# design.net
KiCad netlist of a schematic drawn in Altium Designer
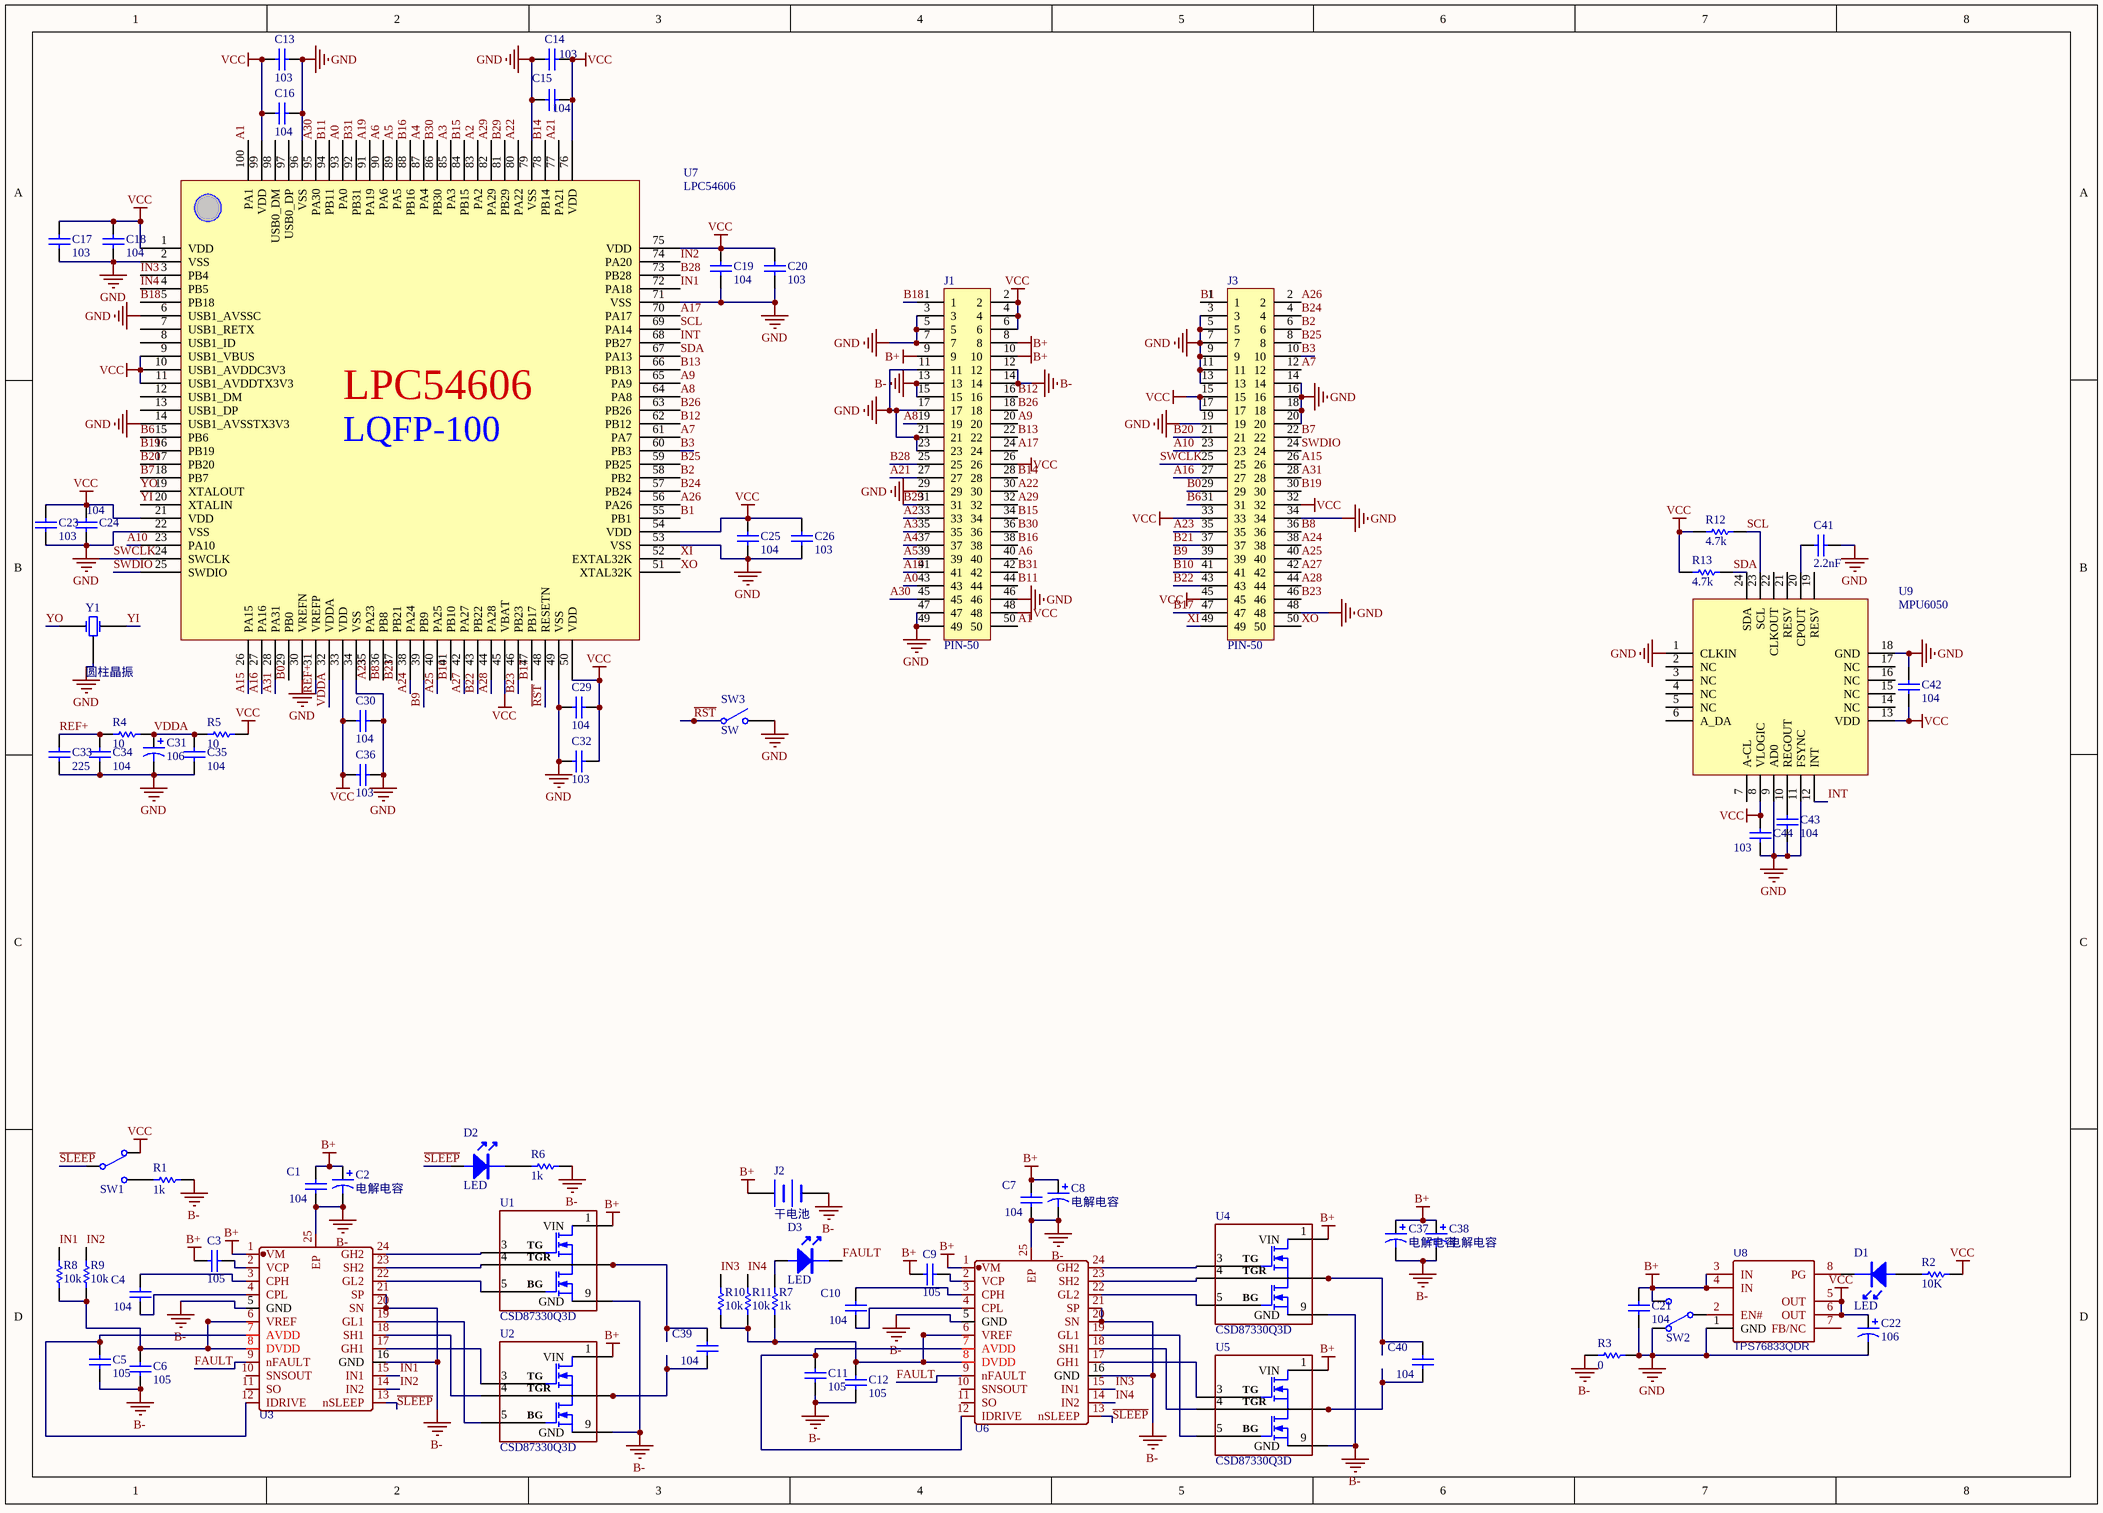
[diagram p0: 原理图.SchDoc]

(export (version "E")
  (design (tool "Eeschema 10.0.6"))
  (components
    (comp (ref "C1")
      (value "104")
      (footprint "C0402")
      (description "Capacitor")
      (fields (field (name "PUBLISHER") "Altium Limited"))
      (libsource (lib "容阻感") (part "电容"))
    )
    (comp (ref "C2")
      (value "电解电容")
      (footprint "贴片电解 4*5.4")
      (description "Polarized Capacitor (Axial)")
      (fields (field (name "PUBLISHER") "Altium Limited"))
      (libsource (lib "容阻感") (part "电解电容"))
    )
    (comp (ref "C3")
      (value "105")
      (footprint "C0603")
      (description "Capacitor")
      (fields (field (name "PUBLISHER") "Altium Limited"))
      (libsource (lib "容阻感") (part "电容"))
    )
    (comp (ref "C4")
      (value "104")
      (footprint "C0402")
      (description "Capacitor")
      (fields (field (name "PUBLISHER") "Altium Limited"))
      (libsource (lib "容阻感") (part "电容"))
    )
    (comp (ref "C5")
      (value "105")
      (footprint "C0402")
      (description "Capacitor")
      (fields (field (name "PUBLISHER") "Altium Limited"))
      (libsource (lib "容阻感") (part "电容"))
    )
    (comp (ref "C6")
      (value "105")
      (footprint "C0402")
      (description "Capacitor")
      (fields (field (name "PUBLISHER") "Altium Limited"))
      (libsource (lib "容阻感") (part "电容"))
    )
    (comp (ref "C7")
      (value "104")
      (footprint "C0402")
      (description "Capacitor")
      (fields (field (name "PUBLISHER") "Altium Limited"))
      (libsource (lib "容阻感") (part "电容"))
    )
    (comp (ref "C8")
      (value "电解电容")
      (footprint "贴片电解 4*5.4")
      (description "Polarized Capacitor (Axial)")
      (fields (field (name "PUBLISHER") "Altium Limited"))
      (libsource (lib "容阻感") (part "电解电容"))
    )
    (comp (ref "C9")
      (value "105")
      (footprint "C0603")
      (description "Capacitor")
      (fields (field (name "PUBLISHER") "Altium Limited"))
      (libsource (lib "容阻感") (part "电容"))
    )
    (comp (ref "C10")
      (value "104")
      (footprint "C0402")
      (description "Capacitor")
      (fields (field (name "PUBLISHER") "Altium Limited"))
      (libsource (lib "容阻感") (part "电容"))
    )
    (comp (ref "C11")
      (value "105")
      (footprint "C0402")
      (description "Capacitor")
      (fields (field (name "PUBLISHER") "Altium Limited"))
      (libsource (lib "容阻感") (part "电容"))
    )
    (comp (ref "C12")
      (value "105")
      (footprint "C0402")
      (description "Capacitor")
      (fields (field (name "PUBLISHER") "Altium Limited"))
      (libsource (lib "容阻感") (part "电容"))
    )
    (comp (ref "C13")
      (value "103")
      (footprint "C0402")
      (description "Capacitor")
      (fields (field (name "PUBLISHER") "Altium Limited"))
      (libsource (lib "容阻感") (part "电容"))
    )
    (comp (ref "C14")
      (value "103")
      (footprint "C0402")
      (description "Capacitor")
      (fields (field (name "PUBLISHER") "Altium Limited"))
      (libsource (lib "容阻感") (part "电容"))
    )
    (comp (ref "C15")
      (value "104")
      (footprint "C0402")
      (description "Capacitor")
      (fields (field (name "PUBLISHER") "Altium Limited"))
      (libsource (lib "容阻感") (part "电容"))
    )
    (comp (ref "C16")
      (value "104")
      (footprint "C0402")
      (description "Capacitor")
      (fields (field (name "PUBLISHER") "Altium Limited"))
      (libsource (lib "容阻感") (part "电容"))
    )
    (comp (ref "C17")
      (value "103")
      (footprint "C0402")
      (description "Capacitor")
      (fields (field (name "PUBLISHER") "Altium Limited"))
      (libsource (lib "容阻感") (part "电容"))
    )
    (comp (ref "C18")
      (value "104")
      (footprint "C0402")
      (description "Capacitor")
      (fields (field (name "PUBLISHER") "Altium Limited"))
      (libsource (lib "容阻感") (part "电容"))
    )
    (comp (ref "C19")
      (value "104")
      (footprint "C0402")
      (description "Capacitor")
      (fields (field (name "PUBLISHER") "Altium Limited"))
      (libsource (lib "容阻感") (part "电容"))
    )
    (comp (ref "C20")
      (value "103")
      (footprint "C0402")
      (description "Capacitor")
      (fields (field (name "PUBLISHER") "Altium Limited"))
      (libsource (lib "容阻感") (part "电容"))
    )
    (comp (ref "C21")
      (value "104")
      (footprint "C0402")
      (description "Capacitor")
      (fields (field (name "PUBLISHER") "Altium Limited"))
      (libsource (lib "容阻感") (part "电容"))
    )
    (comp (ref "C22")
      (value "106")
      (footprint "3216-ce")
      (description "Polarized Capacitor (Axial)")
      (fields (field (name "PUBLISHER") "Altium Limited"))
      (libsource (lib "容阻感") (part "电解电容"))
    )
    (comp (ref "C23")
      (value "103")
      (footprint "C0402")
      (description "Capacitor")
      (fields (field (name "PUBLISHER") "Altium Limited"))
      (libsource (lib "容阻感") (part "电容"))
    )
    (comp (ref "C24")
      (value "104")
      (footprint "C0402")
      (description "Capacitor")
      (fields (field (name "PUBLISHER") "Altium Limited"))
      (libsource (lib "容阻感") (part "电容"))
    )
    (comp (ref "C25")
      (value "104")
      (footprint "C0402")
      (description "Capacitor")
      (fields (field (name "PUBLISHER") "Altium Limited"))
      (libsource (lib "容阻感") (part "电容"))
    )
    (comp (ref "C26")
      (value "103")
      (footprint "C0402")
      (description "Capacitor")
      (fields (field (name "PUBLISHER") "Altium Limited"))
      (libsource (lib "容阻感") (part "电容"))
    )
    (comp (ref "C29")
      (value "104")
      (footprint "C0402")
      (description "Capacitor")
      (fields (field (name "PUBLISHER") "Altium Limited"))
      (libsource (lib "容阻感") (part "电容"))
    )
    (comp (ref "C30")
      (value "104")
      (footprint "C0402")
      (description "Capacitor")
      (fields (field (name "PUBLISHER") "Altium Limited"))
      (libsource (lib "容阻感") (part "电容"))
    )
    (comp (ref "C31")
      (value "106")
      (footprint "3216-ce")
      (description "Polarized Capacitor (Axial)")
      (fields (field (name "PUBLISHER") "Altium Limited"))
      (libsource (lib "容阻感") (part "电解电容"))
    )
    (comp (ref "C32")
      (value "103")
      (footprint "C0402")
      (description "Capacitor")
      (fields (field (name "PUBLISHER") "Altium Limited"))
      (libsource (lib "容阻感") (part "电容"))
    )
    (comp (ref "C33")
      (value "225")
      (footprint "C0603")
      (description "Capacitor")
      (fields (field (name "PUBLISHER") "Altium Limited"))
      (libsource (lib "容阻感") (part "电容"))
    )
    (comp (ref "C34")
      (value "104")
      (footprint "C0402")
      (description "Capacitor")
      (fields (field (name "PUBLISHER") "Altium Limited"))
      (libsource (lib "容阻感") (part "电容"))
    )
    (comp (ref "C35")
      (value "104")
      (footprint "C0402")
      (description "Capacitor")
      (fields (field (name "PUBLISHER") "Altium Limited"))
      (libsource (lib "容阻感") (part "电容"))
    )
    (comp (ref "C36")
      (value "103")
      (footprint "C0402")
      (description "Capacitor")
      (fields (field (name "PUBLISHER") "Altium Limited"))
      (libsource (lib "容阻感") (part "电容"))
    )
    (comp (ref "C37")
      (value "电解电容")
      (footprint "贴片电解 4*5.4")
      (description "Polarized Capacitor (Axial)")
      (fields (field (name "PUBLISHER") "Altium Limited"))
      (libsource (lib "容阻感") (part "电解电容"))
    )
    (comp (ref "C38")
      (value "电解电容")
      (footprint "贴片电解 4*5.4")
      (description "Polarized Capacitor (Axial)")
      (fields (field (name "PUBLISHER") "Altium Limited"))
      (libsource (lib "容阻感") (part "电解电容"))
    )
    (comp (ref "C39")
      (value "104")
      (footprint "C0402")
      (description "Capacitor")
      (fields (field (name "PUBLISHER") "Altium Limited"))
      (libsource (lib "容阻感") (part "电容"))
    )
    (comp (ref "C40")
      (value "104")
      (footprint "C0402")
      (description "Capacitor")
      (fields (field (name "PUBLISHER") "Altium Limited"))
      (libsource (lib "容阻感") (part "电容"))
    )
    (comp (ref "C41")
      (value "2.2nF")
      (footprint "C0402")
      (description "Capacitor")
      (fields (field (name "PUBLISHER") "Altium Limited"))
      (libsource (lib "容阻感") (part "电容"))
    )
    (comp (ref "C42")
      (value "104")
      (footprint "C0402")
      (description "Capacitor")
      (fields (field (name "PUBLISHER") "Altium Limited"))
      (libsource (lib "容阻感") (part "电容"))
    )
    (comp (ref "C43")
      (value "104")
      (footprint "C0402")
      (description "Capacitor")
      (fields (field (name "PUBLISHER") "Altium Limited"))
      (libsource (lib "容阻感") (part "电容"))
    )
    (comp (ref "C44")
      (value "103")
      (footprint "C0402")
      (description "Capacitor")
      (fields (field (name "PUBLISHER") "Altium Limited"))
      (libsource (lib "容阻感") (part "电容"))
    )
    (comp (ref "D1") (value "LED") (footprint "LED 0603G") (libsource (lib "管子、") (part "LED")))
    (comp (ref "D2") (value "LED") (footprint "LED 0603G") (libsource (lib "管子、") (part "LED")))
    (comp (ref "D3") (value "LED") (footprint "LED 0603G") (libsource (lib "管子、") (part "LED")))
    (comp (ref "J1") (value "PIN-50") (footprint "50PDF12-0.5母") (libsource (lib "接插件") (part "PIN-50")))
    (comp (ref "J2")
      (value "干电池")
      (footprint "T接头")
      (description "Battery")
      (libsource (lib "接插件") (part "干电池"))
    )
    (comp (ref "J3") (value "PIN-50") (footprint "50PDF12-0.5母") (libsource (lib "接插件") (part "PIN-50")))
    (comp (ref "R1")
      (value "1k")
      (footprint "R0402")
      (description "Resistor")
      (fields (field (name "PUBLISHER") "Altium Limited"))
      (libsource (lib "容阻感") (part "电阻"))
    )
    (comp (ref "R2")
      (value "10K")
      (footprint "R0402")
      (description "Resistor")
      (fields (field (name "PUBLISHER") "Altium Limited"))
      (libsource (lib "容阻感") (part "电阻"))
    )
    (comp (ref "R3")
      (value "0")
      (footprint "R0603")
      (description "Resistor")
      (fields (field (name "PUBLISHER") "Altium Limited"))
      (libsource (lib "容阻感") (part "电阻"))
    )
    (comp (ref "R4")
      (value "10")
      (footprint "R0603")
      (description "Resistor")
      (fields (field (name "PUBLISHER") "Altium Limited"))
      (libsource (lib "容阻感") (part "电阻"))
    )
    (comp (ref "R5")
      (value "10")
      (footprint "R0603")
      (description "Resistor")
      (fields (field (name "PUBLISHER") "Altium Limited"))
      (libsource (lib "容阻感") (part "电阻"))
    )
    (comp (ref "R6")
      (value "1k")
      (footprint "R0402")
      (description "Resistor")
      (fields (field (name "PUBLISHER") "Altium Limited"))
      (libsource (lib "容阻感") (part "电阻"))
    )
    (comp (ref "R7")
      (value "1k")
      (footprint "R0402")
      (description "Resistor")
      (fields (field (name "PUBLISHER") "Altium Limited"))
      (libsource (lib "容阻感") (part "电阻"))
    )
    (comp (ref "R8")
      (value "10k")
      (footprint "R0402")
      (description "Resistor")
      (fields (field (name "PUBLISHER") "Altium Limited"))
      (libsource (lib "容阻感") (part "电阻"))
    )
    (comp (ref "R9")
      (value "10k")
      (footprint "R0402")
      (description "Resistor")
      (fields (field (name "PUBLISHER") "Altium Limited"))
      (libsource (lib "容阻感") (part "电阻"))
    )
    (comp (ref "R10")
      (value "10k")
      (footprint "R0402")
      (description "Resistor")
      (fields (field (name "PUBLISHER") "Altium Limited"))
      (libsource (lib "容阻感") (part "电阻"))
    )
    (comp (ref "R11")
      (value "10k")
      (footprint "R0402")
      (description "Resistor")
      (fields (field (name "PUBLISHER") "Altium Limited"))
      (libsource (lib "容阻感") (part "电阻"))
    )
    (comp (ref "R12")
      (value "4.7k")
      (footprint "R0402")
      (description "Resistor")
      (fields (field (name "PUBLISHER") "Altium Limited"))
      (libsource (lib "容阻感") (part "电阻"))
    )
    (comp (ref "R13")
      (value "4.7k")
      (footprint "R0402")
      (description "Resistor")
      (fields (field (name "PUBLISHER") "Altium Limited"))
      (libsource (lib "容阻感") (part "电阻"))
    )
    (comp (ref "SW1")
      (value "K3-1235S-K1")
      (footprint "K3-1235S-K1")
      (description "Switch")
      (libsource (lib "接插件") (part "单刀双掷"))
    )
    (comp (ref "SW2")
      (value "K3-1235S-K1")
      (footprint "K3-1235S-K1")
      (description "Switch")
      (libsource (lib "接插件") (part "单刀双掷"))
    )
    (comp (ref "SW3")
      (value "SW")
      (footprint "按键微动开关2")
      (description "Single-Pole, Single-Throw Switch")
      (libsource (lib "接插件") (part "Switch"))
    )
    (comp (ref "U1")
      (value "CSD87330Q3D")
      (footprint "LSON-CLIP-8")
      (description "半桥NMOS")
      (libsource (lib "IC") (part "CSD87330Q3D"))
    )
    (comp (ref "U2")
      (value "CSD87330Q3D")
      (footprint "LSON-CLIP-8")
      (description "半桥NMOS")
      (libsource (lib "IC") (part "CSD87330Q3D"))
    )
    (comp (ref "U3")
      (value "DRV8701ERGET")
      (footprint "VQFN-24_24PIN-L4.00-W4.00-PITCH0.50-EP-TL")
      (description "H桥驱动")
      (fields (field (name "BOM_SUPPLIER PART") "C132049") (field (name "CONTRIBUTOR") "LCSC"))
      (libsource (lib "IC") (part "DRV8701"))
    )
    (comp (ref "U4")
      (value "CSD87330Q3D")
      (footprint "LSON-CLIP-8")
      (description "半桥NMOS")
      (libsource (lib "IC") (part "CSD87330Q3D"))
    )
    (comp (ref "U5")
      (value "CSD87330Q3D")
      (footprint "LSON-CLIP-8")
      (description "半桥NMOS")
      (libsource (lib "IC") (part "CSD87330Q3D"))
    )
    (comp (ref "U6")
      (value "DRV8701ERGET")
      (footprint "VQFN-24_24PIN-L4.00-W4.00-PITCH0.50-EP-TL")
      (description "H桥驱动")
      (fields (field (name "BOM_SUPPLIER PART") "C132049") (field (name "CONTRIBUTOR") "LCSC"))
      (libsource (lib "IC") (part "DRV8701"))
    )
    (comp (ref "U7") (value "LPC54606") (footprint "LQFP100") (libsource (lib "IC") (part "LPC54606BD100")))
    (comp (ref "U8")
      (value "TPS76833QDR")
      (footprint "SOIC8-3.9MM")
      (fields (field (name "BOM_SUPPLIER PART") "C16002"))
      (libsource (lib "IC") (part "TPS76833QDR"))
    )
    (comp (ref "U9") (value "MPU6050") (footprint "QFN-24_4x4x05P") (libsource (lib "IC") (part "MPU6050")))
    (comp (ref "Y1")
      (value "圆柱晶振")
      (footprint "OSC-3213CSTSE800G52-R0")
      (libsource (lib "IC") (part "XTAL_3Pin"))
    )
  )
  (nets
    (net (code "1") (name "/A0") (class "Default")
      (node (ref "J1") (pin "43") (pinfunction "43_43") (pintype "passive"))
      (node (ref "U7") (pin "93") (pinfunction "PA0_93") (pintype "passive"))
    )
    (net (code "2") (name "/A1") (class "Default")
      (node (ref "J1") (pin "50") (pinfunction "50_50") (pintype "passive"))
      (node (ref "U7") (pin "100") (pinfunction "PA1_100") (pintype "passive"))
    )
    (net (code "3") (name "/A2") (class "Default")
      (node (ref "J1") (pin "33") (pinfunction "33_33") (pintype "passive"))
      (node (ref "U7") (pin "83") (pinfunction "PA2_83") (pintype "passive"))
    )
    (net (code "4") (name "/A3") (class "Default")
      (node (ref "J1") (pin "35") (pinfunction "35_35") (pintype "passive"))
      (node (ref "U7") (pin "85") (pinfunction "PA3_85") (pintype "passive"))
    )
    (net (code "5") (name "/A4") (class "Default")
      (node (ref "J1") (pin "37") (pinfunction "37_37") (pintype "passive"))
      (node (ref "U7") (pin "87") (pinfunction "PA4_87") (pintype "passive"))
    )
    (net (code "6") (name "/A5") (class "Default")
      (node (ref "J1") (pin "39") (pinfunction "39_39") (pintype "passive"))
      (node (ref "U7") (pin "89") (pinfunction "PA5_89") (pintype "passive"))
    )
    (net (code "7") (name "/A6") (class "Default")
      (node (ref "J1") (pin "40") (pinfunction "40_40") (pintype "passive"))
      (node (ref "U7") (pin "90") (pinfunction "PA6_90") (pintype "passive"))
    )
    (net (code "8") (name "/A7") (class "Default")
      (node (ref "J3") (pin "12") (pinfunction "12_12") (pintype "passive"))
      (node (ref "U7") (pin "61") (pinfunction "PA7_61") (pintype "passive"))
    )
    (net (code "9") (name "/A8") (class "Default")
      (node (ref "J1") (pin "19") (pinfunction "19_19") (pintype "passive"))
      (node (ref "U7") (pin "64") (pinfunction "PA8_64") (pintype "passive"))
    )
    (net (code "10") (name "/A9") (class "Default")
      (node (ref "J1") (pin "20") (pinfunction "20_20") (pintype "passive"))
      (node (ref "U7") (pin "65") (pinfunction "PA9_65") (pintype "passive"))
    )
    (net (code "11") (name "/A10") (class "Default")
      (node (ref "J3") (pin "23") (pinfunction "23_23") (pintype "passive"))
      (node (ref "U7") (pin "23") (pinfunction "PA10_23") (pintype "passive"))
    )
    (net (code "12") (name "/A15") (class "Default")
      (node (ref "J3") (pin "26") (pinfunction "26_26") (pintype "passive"))
      (node (ref "U7") (pin "26") (pinfunction "PA15_26") (pintype "passive"))
    )
    (net (code "13") (name "/A16") (class "Default")
      (node (ref "J3") (pin "27") (pinfunction "27_27") (pintype "passive"))
      (node (ref "U7") (pin "27") (pinfunction "PA16_27") (pintype "passive"))
    )
    (net (code "14") (name "/A17") (class "Default")
      (node (ref "J1") (pin "24") (pinfunction "24_24") (pintype "passive"))
      (node (ref "U7") (pin "70") (pinfunction "PA17_70") (pintype "passive"))
    )
    (net (code "15") (name "/A19") (class "Default")
      (node (ref "J1") (pin "41") (pinfunction "41_41") (pintype "passive"))
      (node (ref "U7") (pin "91") (pinfunction "PA19_91") (pintype "passive"))
    )
    (net (code "16") (name "/A21") (class "Default")
      (node (ref "J1") (pin "27") (pinfunction "27_27") (pintype "passive"))
      (node (ref "U7") (pin "77") (pinfunction "PA21_77") (pintype "passive"))
    )
    (net (code "17") (name "/A22") (class "Default")
      (node (ref "J1") (pin "30") (pinfunction "30_30") (pintype "passive"))
      (node (ref "U7") (pin "80") (pinfunction "PA22_80") (pintype "passive"))
    )
    (net (code "18") (name "/A23") (class "Default")
      (node (ref "J3") (pin "35") (pinfunction "35_35") (pintype "passive"))
      (node (ref "U7") (pin "35") (pinfunction "PA23_35") (pintype "passive"))
    )
    (net (code "19") (name "/A24") (class "Default")
      (node (ref "J3") (pin "38") (pinfunction "38_38") (pintype "passive"))
      (node (ref "U7") (pin "38") (pinfunction "PA24_38") (pintype "passive"))
    )
    (net (code "20") (name "/A25") (class "Default")
      (node (ref "J3") (pin "40") (pinfunction "40_40") (pintype "passive"))
      (node (ref "U7") (pin "40") (pinfunction "PA25_40") (pintype "passive"))
    )
    (net (code "21") (name "/A26") (class "Default")
      (node (ref "J3") (pin "2") (pinfunction "2_2") (pintype "passive"))
      (node (ref "U7") (pin "56") (pinfunction "PA26_56") (pintype "passive"))
    )
    (net (code "22") (name "/A27") (class "Default")
      (node (ref "J3") (pin "42") (pinfunction "42_42") (pintype "passive"))
      (node (ref "U7") (pin "42") (pinfunction "PA27_42") (pintype "passive"))
    )
    (net (code "23") (name "/A28") (class "Default")
      (node (ref "J3") (pin "44") (pinfunction "44_44") (pintype "passive"))
      (node (ref "U7") (pin "44") (pinfunction "PA28_44") (pintype "passive"))
    )
    (net (code "24") (name "/A29") (class "Default")
      (node (ref "J1") (pin "32") (pinfunction "32_32") (pintype "passive"))
      (node (ref "U7") (pin "82") (pinfunction "PA29_82") (pintype "passive"))
    )
    (net (code "25") (name "/A30") (class "Default")
      (node (ref "J1") (pin "45") (pinfunction "45_45") (pintype "passive"))
      (node (ref "U7") (pin "95") (pinfunction "PA30_95") (pintype "passive"))
    )
    (net (code "26") (name "/A31") (class "Default")
      (node (ref "J3") (pin "28") (pinfunction "28_28") (pintype "passive"))
      (node (ref "U7") (pin "28") (pinfunction "PA31_28") (pintype "passive"))
    )
    (net (code "27") (name "/B0") (class "Default")
      (node (ref "J3") (pin "29") (pinfunction "29_29") (pintype "passive"))
      (node (ref "U7") (pin "29") (pinfunction "PB0_29") (pintype "passive"))
    )
    (net (code "28") (name "/B1") (class "Default")
      (node (ref "J3") (pin "1") (pinfunction "1_1") (pintype "passive"))
      (node (ref "U7") (pin "55") (pinfunction "PB1_55") (pintype "passive"))
    )
    (net (code "29") (name "/B2") (class "Default")
      (node (ref "J3") (pin "6") (pinfunction "6_6") (pintype "passive"))
      (node (ref "U7") (pin "58") (pinfunction "PB2_58") (pintype "passive"))
    )
    (net (code "30") (name "/B3") (class "Default")
      (node (ref "J3") (pin "10") (pinfunction "10_10") (pintype "passive"))
      (node (ref "U7") (pin "60") (pinfunction "PB3_60") (pintype "passive"))
    )
    (net (code "31") (name "/B6") (class "Default")
      (node (ref "J3") (pin "31") (pinfunction "31_31") (pintype "passive"))
      (node (ref "U7") (pin "15") (pinfunction "PB6_15") (pintype "passive"))
    )
    (net (code "32") (name "/B7") (class "Default")
      (node (ref "J3") (pin "22") (pinfunction "22_22") (pintype "passive"))
      (node (ref "U7") (pin "18") (pinfunction "PB7_18") (pintype "passive"))
    )
    (net (code "33") (name "/B8") (class "Default")
      (node (ref "J3") (pin "36") (pinfunction "36_36") (pintype "passive"))
      (node (ref "U7") (pin "36") (pinfunction "PB8_36") (pintype "passive"))
    )
    (net (code "34") (name "/B9") (class "Default")
      (node (ref "J3") (pin "39") (pinfunction "39_39") (pintype "passive"))
      (node (ref "U7") (pin "39") (pinfunction "PB9_39") (pintype "passive"))
    )
    (net (code "35") (name "/B10") (class "Default")
      (node (ref "J3") (pin "41") (pinfunction "41_41") (pintype "passive"))
      (node (ref "U7") (pin "41") (pinfunction "PB10_41") (pintype "passive"))
    )
    (net (code "36") (name "/B11") (class "Default")
      (node (ref "J1") (pin "44") (pinfunction "44_44") (pintype "passive"))
      (node (ref "U7") (pin "94") (pinfunction "PB11_94") (pintype "passive"))
    )
    (net (code "37") (name "/B12") (class "Default")
      (node (ref "J1") (pin "16") (pinfunction "16_16") (pintype "passive"))
      (node (ref "U7") (pin "62") (pinfunction "PB12_62") (pintype "passive"))
    )
    (net (code "38") (name "/B13") (class "Default")
      (node (ref "J1") (pin "22") (pinfunction "22_22") (pintype "passive"))
      (node (ref "U7") (pin "66") (pinfunction "PB13_66") (pintype "passive"))
    )
    (net (code "39") (name "/B14") (class "Default")
      (node (ref "J1") (pin "28") (pinfunction "28_28") (pintype "passive"))
      (node (ref "U7") (pin "78") (pinfunction "PB14_78") (pintype "passive"))
    )
    (net (code "40") (name "/B15") (class "Default")
      (node (ref "J1") (pin "34") (pinfunction "34_34") (pintype "passive"))
      (node (ref "U7") (pin "84") (pinfunction "PB15_84") (pintype "passive"))
    )
    (net (code "41") (name "/B16") (class "Default")
      (node (ref "J1") (pin "38") (pinfunction "38_38") (pintype "passive"))
      (node (ref "U7") (pin "88") (pinfunction "PB16_88") (pintype "passive"))
    )
    (net (code "42") (name "/B17") (class "Default")
      (node (ref "J3") (pin "47") (pinfunction "47_47") (pintype "passive"))
      (node (ref "U7") (pin "47") (pinfunction "PB17_47") (pintype "passive"))
    )
    (net (code "43") (name "/B18") (class "Default")
      (node (ref "J1") (pin "1") (pinfunction "1_1") (pintype "passive"))
      (node (ref "U7") (pin "5") (pinfunction "PB18_5") (pintype "passive"))
    )
    (net (code "44") (name "/B19") (class "Default")
      (node (ref "J3") (pin "30") (pinfunction "30_30") (pintype "passive"))
      (node (ref "U7") (pin "16") (pinfunction "PB19_16") (pintype "passive"))
    )
    (net (code "45") (name "/B20") (class "Default")
      (node (ref "J3") (pin "21") (pinfunction "21_21") (pintype "passive"))
      (node (ref "U7") (pin "17") (pinfunction "PB20_17") (pintype "passive"))
    )
    (net (code "46") (name "/B21") (class "Default")
      (node (ref "J3") (pin "37") (pinfunction "37_37") (pintype "passive"))
      (node (ref "U7") (pin "37") (pinfunction "PB21_37") (pintype "passive"))
    )
    (net (code "47") (name "/B22") (class "Default")
      (node (ref "J3") (pin "43") (pinfunction "43_43") (pintype "passive"))
      (node (ref "U7") (pin "43") (pinfunction "PB22_43") (pintype "passive"))
    )
    (net (code "48") (name "/B23") (class "Default")
      (node (ref "J3") (pin "46") (pinfunction "46_46") (pintype "passive"))
      (node (ref "U7") (pin "46") (pinfunction "PB23_46") (pintype "passive"))
    )
    (net (code "49") (name "/B24") (class "Default")
      (node (ref "J3") (pin "4") (pinfunction "4_4") (pintype "passive"))
      (node (ref "U7") (pin "57") (pinfunction "PB24_57") (pintype "passive"))
    )
    (net (code "50") (name "/B25") (class "Default")
      (node (ref "J3") (pin "8") (pinfunction "8_8") (pintype "passive"))
      (node (ref "U7") (pin "59") (pinfunction "PB25_59") (pintype "passive"))
    )
    (net (code "51") (name "/B26") (class "Default")
      (node (ref "J1") (pin "18") (pinfunction "18_18") (pintype "passive"))
      (node (ref "U7") (pin "63") (pinfunction "PB26_63") (pintype "passive"))
    )
    (net (code "52") (name "/B28") (class "Default")
      (node (ref "J1") (pin "25") (pinfunction "25_25") (pintype "passive"))
      (node (ref "U7") (pin "73") (pinfunction "PB28_73") (pintype "passive"))
    )
    (net (code "53") (name "/B29") (class "Default")
      (node (ref "J1") (pin "31") (pinfunction "31_31") (pintype "passive"))
      (node (ref "U7") (pin "81") (pinfunction "PB29_81") (pintype "passive"))
    )
    (net (code "54") (name "/B30") (class "Default")
      (node (ref "J1") (pin "36") (pinfunction "36_36") (pintype "passive"))
      (node (ref "U7") (pin "86") (pinfunction "PB30_86") (pintype "passive"))
    )
    (net (code "55") (name "/B31") (class "Default")
      (node (ref "J1") (pin "42") (pinfunction "42_42") (pintype "passive"))
      (node (ref "U7") (pin "92") (pinfunction "PB31_92") (pintype "passive"))
    )
    (net (code "56") (name "/FAULT") (class "Default")
      (node (ref "D3") (pin "K") (pinfunction "2_K") (pintype "passive"))
      (node (ref "U3") (pin "9") (pinfunction "nFAULT_9") (pintype "passive"))
      (node (ref "U6") (pin "9") (pinfunction "nFAULT_9") (pintype "passive"))
    )
    (net (code "57") (name "/IN1") (class "Default")
      (node (ref "R8") (pin "1") (pinfunction "1_1") (pintype "passive"))
      (node (ref "U3") (pin "15") (pinfunction "IN1_15") (pintype "passive"))
      (node (ref "U7") (pin "72") (pinfunction "PA18_72") (pintype "passive"))
    )
    (net (code "58") (name "/IN2") (class "Default")
      (node (ref "R9") (pin "1") (pinfunction "1_1") (pintype "passive"))
      (node (ref "U3") (pin "14") (pinfunction "IN2_14") (pintype "passive"))
      (node (ref "U7") (pin "74") (pinfunction "PA20_74") (pintype "passive"))
    )
    (net (code "59") (name "/IN3") (class "Default")
      (node (ref "R10") (pin "1") (pinfunction "1_1") (pintype "passive"))
      (node (ref "U6") (pin "15") (pinfunction "IN1_15") (pintype "passive"))
      (node (ref "U7") (pin "3") (pinfunction "PB4_3") (pintype "passive"))
    )
    (net (code "60") (name "/IN4") (class "Default")
      (node (ref "R11") (pin "1") (pinfunction "1_1") (pintype "passive"))
      (node (ref "U6") (pin "14") (pinfunction "IN2_14") (pintype "passive"))
      (node (ref "U7") (pin "4") (pinfunction "PB5_4") (pintype "passive"))
    )
    (net (code "61") (name "/INT") (class "Default")
      (node (ref "U7") (pin "68") (pinfunction "PB27_68") (pintype "passive"))
      (node (ref "U9") (pin "12") (pinfunction "INT_12") (pintype "passive"))
    )
    (net (code "62") (name "/REF+") (class "Default")
      (node (ref "C33") (pin "2") (pinfunction "2_2") (pintype "passive"))
      (node (ref "C34") (pin "2") (pinfunction "2_2") (pintype "passive"))
      (node (ref "R4") (pin "2") (pinfunction "2_2") (pintype "passive"))
      (node (ref "U7") (pin "31") (pinfunction "VREFP_31") (pintype "passive"))
    )
    (net (code "63") (name "/RST") (class "Default")
      (node (ref "SW3") (pin "1") (pinfunction "COMMON_1") (pintype "passive"))
      (node (ref "U7") (pin "48") (pinfunction "RESETN_48") (pintype "passive"))
    )
    (net (code "64") (name "/SCL") (class "Default")
      (node (ref "R12") (pin "2") (pinfunction "2_2") (pintype "passive"))
      (node (ref "U7") (pin "69") (pinfunction "PA14_69") (pintype "passive"))
      (node (ref "U9") (pin "23") (pinfunction "SCL_23") (pintype "passive"))
    )
    (net (code "65") (name "/SDA") (class "Default")
      (node (ref "R13") (pin "2") (pinfunction "2_2") (pintype "passive"))
      (node (ref "U7") (pin "67") (pinfunction "PA13_67") (pintype "passive"))
      (node (ref "U9") (pin "24") (pinfunction "SDA_24") (pintype "passive"))
    )
    (net (code "66") (name "/SLEEP") (class "Default")
      (node (ref "D2") (pin "A") (pinfunction "1_A") (pintype "passive"))
      (node (ref "SW1") (pin "2") (pinfunction "2_2") (pintype "passive"))
      (node (ref "U3") (pin "13") (pinfunction "nSLEEP_13") (pintype "passive"))
      (node (ref "U6") (pin "13") (pinfunction "nSLEEP_13") (pintype "passive"))
    )
    (net (code "67") (name "/SWCLK") (class "Default")
      (node (ref "J3") (pin "25") (pinfunction "25_25") (pintype "passive"))
      (node (ref "U7") (pin "24") (pinfunction "SWCLK_24") (pintype "passive"))
    )
    (net (code "68") (name "/SWDIO") (class "Default")
      (node (ref "J3") (pin "24") (pinfunction "24_24") (pintype "passive"))
      (node (ref "U7") (pin "25") (pinfunction "SWDIO_25") (pintype "passive"))
    )
    (net (code "69") (name "/VDDA") (class "Default")
      (node (ref "C31") (pin "1") (pinfunction "1_1") (pintype "passive"))
      (node (ref "C35") (pin "2") (pinfunction "2_2") (pintype "passive"))
      (node (ref "R4") (pin "1") (pinfunction "1_1") (pintype "passive"))
      (node (ref "R5") (pin "2") (pinfunction "2_2") (pintype "passive"))
      (node (ref "U7") (pin "32") (pinfunction "VDDA_32") (pintype "passive"))
    )
    (net (code "70") (name "/XI") (class "Default")
      (node (ref "J3") (pin "49") (pinfunction "49_49") (pintype "passive"))
      (node (ref "U7") (pin "52") (pinfunction "EXTAL32K_52") (pintype "passive"))
    )
    (net (code "71") (name "/XO") (class "Default")
      (node (ref "J3") (pin "50") (pinfunction "50_50") (pintype "passive"))
      (node (ref "U7") (pin "51") (pinfunction "XTAL32K_51") (pintype "passive"))
    )
    (net (code "72") (name "/YI") (class "Default")
      (node (ref "U7") (pin "20") (pinfunction "XTALIN_20") (pintype "passive"))
      (node (ref "Y1") (pin "2") (pinfunction "OSC2_2") (pintype "passive"))
    )
    (net (code "73") (name "/YO") (class "Default")
      (node (ref "U7") (pin "19") (pinfunction "XTALOUT_19") (pintype "passive"))
      (node (ref "Y1") (pin "1") (pinfunction "OSC1_1") (pintype "passive"))
    )
    (net (code "74") (name "B+") (class "Default")
      (node (ref "C1") (pin "2") (pinfunction "2_2") (pintype "passive"))
      (node (ref "C2") (pin "1") (pinfunction "1_1") (pintype "passive"))
      (node (ref "C21") (pin "2") (pinfunction "2_2") (pintype "passive"))
      (node (ref "C3") (pin "1") (pinfunction "1_1") (pintype "passive"))
      (node (ref "C37") (pin "1") (pinfunction "1_1") (pintype "passive"))
      (node (ref "C38") (pin "1") (pinfunction "1_1") (pintype "passive"))
      (node (ref "C7") (pin "2") (pinfunction "2_2") (pintype "passive"))
      (node (ref "C8") (pin "1") (pinfunction "1_1") (pintype "passive"))
      (node (ref "C9") (pin "1") (pinfunction "1_1") (pintype "passive"))
      (node (ref "J1") (pin "10") (pinfunction "10_10") (pintype "passive"))
      (node (ref "J1") (pin "8") (pinfunction "8_8") (pintype "passive"))
      (node (ref "J1") (pin "9") (pinfunction "9_9") (pintype "passive"))
      (node (ref "J2") (pin "1") (pinfunction "+_1") (pintype "passive"))
      (node (ref "SW2") (pin "3") (pinfunction "3_3") (pintype "passive"))
      (node (ref "U1") (pin "1") (pinfunction "VIN_1") (pintype "passive"))
      (node (ref "U2") (pin "1") (pinfunction "VIN_1") (pintype "passive"))
      (node (ref "U3") (pin "1") (pinfunction "VM_1") (pintype "passive"))
      (node (ref "U4") (pin "1") (pinfunction "VIN_1") (pintype "passive"))
      (node (ref "U5") (pin "1") (pinfunction "VIN_1") (pintype "passive"))
      (node (ref "U6") (pin "1") (pinfunction "VM_1") (pintype "passive"))
      (node (ref "U8") (pin "3") (pinfunction "IN_3") (pintype "passive"))
      (node (ref "U8") (pin "4") (pinfunction "IN_4") (pintype "passive"))
    )
    (net (code "75") (name "B-") (class "Default")
      (node (ref "C1") (pin "1") (pinfunction "1_1") (pintype "passive"))
      (node (ref "C11") (pin "1") (pinfunction "1_1") (pintype "passive"))
      (node (ref "C12") (pin "1") (pinfunction "1_1") (pintype "passive"))
      (node (ref "C2") (pin "2") (pinfunction "2_2") (pintype "passive"))
      (node (ref "C37") (pin "2") (pinfunction "2_2") (pintype "passive"))
      (node (ref "C38") (pin "2") (pinfunction "2_2") (pintype "passive"))
      (node (ref "C5") (pin "1") (pinfunction "1_1") (pintype "passive"))
      (node (ref "C6") (pin "1") (pinfunction "1_1") (pintype "passive"))
      (node (ref "C7") (pin "1") (pinfunction "1_1") (pintype "passive"))
      (node (ref "C8") (pin "2") (pinfunction "2_2") (pintype "passive"))
      (node (ref "J1") (pin "12") (pinfunction "12_12") (pintype "passive"))
      (node (ref "J1") (pin "13") (pinfunction "13_13") (pintype "passive"))
      (node (ref "J1") (pin "14") (pinfunction "14_14") (pintype "passive"))
      (node (ref "J1") (pin "15") (pinfunction "15_15") (pintype "passive"))
      (node (ref "J2") (pin "2") (pinfunction "-_2") (pintype "passive"))
      (node (ref "R1") (pin "1") (pinfunction "1_1") (pintype "passive"))
      (node (ref "R3") (pin "2") (pinfunction "2_2") (pintype "passive"))
      (node (ref "R6") (pin "2") (pinfunction "2_2") (pintype "passive"))
      (node (ref "U1") (pin "9") (pinfunction "GND_9") (pintype "passive"))
      (node (ref "U2") (pin "9") (pinfunction "GND_9") (pintype "passive"))
      (node (ref "U3") (pin "16") (pinfunction "GND_16") (pintype "passive"))
      (node (ref "U3") (pin "20") (pinfunction "SN_20") (pintype "passive"))
      (node (ref "U3") (pin "21") (pinfunction "SP_21") (pintype "passive"))
      (node (ref "U3") (pin "25") (pinfunction "EP_25") (pintype "passive"))
      (node (ref "U3") (pin "5") (pinfunction "GND_5") (pintype "passive"))
      (node (ref "U4") (pin "9") (pinfunction "GND_9") (pintype "passive"))
      (node (ref "U5") (pin "9") (pinfunction "GND_9") (pintype "passive"))
      (node (ref "U6") (pin "16") (pinfunction "GND_16") (pintype "passive"))
      (node (ref "U6") (pin "20") (pinfunction "SN_20") (pintype "passive"))
      (node (ref "U6") (pin "21") (pinfunction "SP_21") (pintype "passive"))
      (node (ref "U6") (pin "25") (pinfunction "EP_25") (pintype "passive"))
      (node (ref "U6") (pin "5") (pinfunction "GND_5") (pintype "passive"))
    )
    (net (code "76") (name "GND") (class "Default")
      (node (ref "C13") (pin "2") (pinfunction "2_2") (pintype "passive"))
      (node (ref "C14") (pin "1") (pinfunction "1_1") (pintype "passive"))
      (node (ref "C15") (pin "1") (pinfunction "1_1") (pintype "passive"))
      (node (ref "C16") (pin "2") (pinfunction "2_2") (pintype "passive"))
      (node (ref "C17") (pin "1") (pinfunction "1_1") (pintype "passive"))
      (node (ref "C18") (pin "1") (pinfunction "1_1") (pintype "passive"))
      (node (ref "C19") (pin "2") (pinfunction "2_2") (pintype "passive"))
      (node (ref "C20") (pin "2") (pinfunction "2_2") (pintype "passive"))
      (node (ref "C21") (pin "1") (pinfunction "1_1") (pintype "passive"))
      (node (ref "C22") (pin "2") (pinfunction "2_2") (pintype "passive"))
      (node (ref "C23") (pin "1") (pinfunction "1_1") (pintype "passive"))
      (node (ref "C24") (pin "1") (pinfunction "1_1") (pintype "passive"))
      (node (ref "C25") (pin "2") (pinfunction "2_2") (pintype "passive"))
      (node (ref "C26") (pin "2") (pinfunction "2_2") (pintype "passive"))
      (node (ref "C29") (pin "2") (pinfunction "2_2") (pintype "passive"))
      (node (ref "C30") (pin "1") (pinfunction "1_1") (pintype "passive"))
      (node (ref "C31") (pin "2") (pinfunction "2_2") (pintype "passive"))
      (node (ref "C32") (pin "2") (pinfunction "2_2") (pintype "passive"))
      (node (ref "C33") (pin "1") (pinfunction "1_1") (pintype "passive"))
      (node (ref "C34") (pin "1") (pinfunction "1_1") (pintype "passive"))
      (node (ref "C35") (pin "1") (pinfunction "1_1") (pintype "passive"))
      (node (ref "C36") (pin "1") (pinfunction "1_1") (pintype "passive"))
      (node (ref "C41") (pin "2") (pinfunction "2_2") (pintype "passive"))
      (node (ref "C42") (pin "1") (pinfunction "1_1") (pintype "passive"))
      (node (ref "C43") (pin "2") (pinfunction "2_2") (pintype "passive"))
      (node (ref "C44") (pin "2") (pinfunction "2_2") (pintype "passive"))
      (node (ref "J1") (pin "11") (pinfunction "11_11") (pintype "passive"))
      (node (ref "J1") (pin "17") (pinfunction "17_17") (pintype "passive"))
      (node (ref "J1") (pin "21") (pinfunction "21_21") (pintype "passive"))
      (node (ref "J1") (pin "23") (pinfunction "23_23") (pintype "passive"))
      (node (ref "J1") (pin "29") (pinfunction "29_29") (pintype "passive"))
      (node (ref "J1") (pin "3") (pinfunction "3_3") (pintype "passive"))
      (node (ref "J1") (pin "46") (pinfunction "46_46") (pintype "passive"))
      (node (ref "J1") (pin "47") (pinfunction "47_47") (pintype "passive"))
      (node (ref "J1") (pin "49") (pinfunction "49_49") (pintype "passive"))
      (node (ref "J1") (pin "5") (pinfunction "5_5") (pintype "passive"))
      (node (ref "J1") (pin "7") (pinfunction "7_7") (pintype "passive"))
      (node (ref "J3") (pin "11") (pinfunction "11_11") (pintype "passive"))
      (node (ref "J3") (pin "13") (pinfunction "13_13") (pintype "passive"))
      (node (ref "J3") (pin "14") (pinfunction "14_14") (pintype "passive"))
      (node (ref "J3") (pin "16") (pinfunction "16_16") (pintype "passive"))
      (node (ref "J3") (pin "18") (pinfunction "18_18") (pintype "passive"))
      (node (ref "J3") (pin "19") (pinfunction "19_19") (pintype "passive"))
      (node (ref "J3") (pin "20") (pinfunction "20_20") (pintype "passive"))
      (node (ref "J3") (pin "3") (pinfunction "3_3") (pintype "passive"))
      (node (ref "J3") (pin "34") (pinfunction "34_34") (pintype "passive"))
      (node (ref "J3") (pin "48") (pinfunction "48_48") (pintype "passive"))
      (node (ref "J3") (pin "5") (pinfunction "5_5") (pintype "passive"))
      (node (ref "J3") (pin "7") (pinfunction "7_7") (pintype "passive"))
      (node (ref "J3") (pin "9") (pinfunction "9_9") (pintype "passive"))
      (node (ref "R3") (pin "1") (pinfunction "1_1") (pintype "passive"))
      (node (ref "SW2") (pin "1") (pinfunction "1_1") (pintype "passive"))
      (node (ref "SW3") (pin "2") (pinfunction "NO_2") (pintype "passive"))
      (node (ref "U7") (pin "14") (pinfunction "USB1_AVSSTX3V3_14") (pintype "passive"))
      (node (ref "U7") (pin "2") (pinfunction "VSS_2") (pintype "passive"))
      (node (ref "U7") (pin "22") (pinfunction "VSS_22") (pintype "passive"))
      (node (ref "U7") (pin "30") (pinfunction "VREFN_30") (pintype "passive"))
      (node (ref "U7") (pin "34") (pinfunction "VSS_34") (pintype "passive"))
      (node (ref "U7") (pin "49") (pinfunction "VSS_49") (pintype "passive"))
      (node (ref "U7") (pin "53") (pinfunction "VSS_53") (pintype "passive"))
      (node (ref "U7") (pin "6") (pinfunction "USB1_AVSSC_6") (pintype "passive"))
      (node (ref "U7") (pin "71") (pinfunction "VSS_71") (pintype "passive"))
      (node (ref "U7") (pin "79") (pinfunction "VSS_79") (pintype "passive"))
      (node (ref "U7") (pin "96") (pinfunction "VSS_96") (pintype "passive"))
      (node (ref "U8") (pin "1") (pinfunction "GND_1") (pintype "passive"))
      (node (ref "U9") (pin "1") (pinfunction "CLKIN_1") (pintype "passive"))
      (node (ref "U9") (pin "11") (pinfunction "FSYNC_11") (pintype "passive"))
      (node (ref "U9") (pin "18") (pinfunction "GND_18") (pintype "passive"))
      (node (ref "U9") (pin "9") (pinfunction "AD0_9") (pintype "passive"))
      (node (ref "Y1") (pin "3") (pinfunction "OSC2_3") (pintype "passive"))
    )
    (net (code "77") (name "Net-(C39-Pad1)") (class "Default")
      (node (ref "C39") (pin "1") (pinfunction "1_1") (pintype "passive"))
      (node (ref "U2") (pin "6") (pinfunction "SW_6") (pintype "passive"))
      (node (ref "U2") (pin "7") (pinfunction "SW_7") (pintype "passive"))
      (node (ref "U2") (pin "8") (pinfunction "SW_8") (pintype "passive"))
    )
    (net (code "78") (name "Net-(C39-Pad2)") (class "Default")
      (node (ref "C39") (pin "2") (pinfunction "2_2") (pintype "passive"))
      (node (ref "U1") (pin "6") (pinfunction "SW_6") (pintype "passive"))
      (node (ref "U1") (pin "7") (pinfunction "SW_7") (pintype "passive"))
      (node (ref "U1") (pin "8") (pinfunction "SW_8") (pintype "passive"))
    )
    (net (code "79") (name "Net-(C40-Pad1)") (class "Default")
      (node (ref "C40") (pin "1") (pinfunction "1_1") (pintype "passive"))
      (node (ref "U5") (pin "6") (pinfunction "SW_6") (pintype "passive"))
      (node (ref "U5") (pin "7") (pinfunction "SW_7") (pintype "passive"))
      (node (ref "U5") (pin "8") (pinfunction "SW_8") (pintype "passive"))
    )
    (net (code "80") (name "Net-(C40-Pad2)") (class "Default")
      (node (ref "C40") (pin "2") (pinfunction "2_2") (pintype "passive"))
      (node (ref "U4") (pin "6") (pinfunction "SW_6") (pintype "passive"))
      (node (ref "U4") (pin "7") (pinfunction "SW_7") (pintype "passive"))
      (node (ref "U4") (pin "8") (pinfunction "SW_8") (pintype "passive"))
    )
    (net (code "81") (name "Net-(D1-1)") (class "Default")
      (node (ref "D1") (pin "A") (pinfunction "1_A") (pintype "passive"))
      (node (ref "R2") (pin "2") (pinfunction "2_2") (pintype "passive"))
    )
    (net (code "82") (name "Net-(D1-2)") (class "Default")
      (node (ref "D1") (pin "K") (pinfunction "2_K") (pintype "passive"))
      (node (ref "U8") (pin "8") (pinfunction "PG_8") (pintype "passive"))
    )
    (net (code "83") (name "Net-(D2-2)") (class "Default")
      (node (ref "D2") (pin "K") (pinfunction "2_K") (pintype "passive"))
      (node (ref "R6") (pin "1") (pinfunction "1_1") (pintype "passive"))
    )
    (net (code "84") (name "Net-(D3-1)") (class "Default")
      (node (ref "D3") (pin "A") (pinfunction "1_A") (pintype "passive"))
      (node (ref "R7") (pin "1") (pinfunction "1_1") (pintype "passive"))
    )
    (net (code "85") (name "Net-(R1-Pad2)") (class "Default")
      (node (ref "R1") (pin "2") (pinfunction "2_2") (pintype "passive"))
      (node (ref "SW1") (pin "3") (pinfunction "3_3") (pintype "passive"))
    )
    (net (code "86") (name "Net-(U1-BG)") (class "Default")
      (node (ref "U1") (pin "5") (pinfunction "BG_5") (pintype "passive"))
      (node (ref "U3") (pin "22") (pinfunction "GL2_22") (pintype "passive"))
    )
    (net (code "87") (name "Net-(U1-TG)") (class "Default")
      (node (ref "U1") (pin "3") (pinfunction "TG_3") (pintype "passive"))
      (node (ref "U3") (pin "24") (pinfunction "GH2_24") (pintype "passive"))
    )
    (net (code "88") (name "Net-(U1-TGR)") (class "Default")
      (node (ref "U1") (pin "4") (pinfunction "TGR_4") (pintype "passive"))
      (node (ref "U3") (pin "23") (pinfunction "SH2_23") (pintype "passive"))
    )
    (net (code "89") (name "Net-(U2-BG)") (class "Default")
      (node (ref "U2") (pin "5") (pinfunction "BG_5") (pintype "passive"))
      (node (ref "U3") (pin "19") (pinfunction "GL1_19") (pintype "passive"))
    )
    (net (code "90") (name "Net-(U2-TG)") (class "Default")
      (node (ref "U2") (pin "3") (pinfunction "TG_3") (pintype "passive"))
      (node (ref "U3") (pin "17") (pinfunction "GH1_17") (pintype "passive"))
    )
    (net (code "91") (name "Net-(U2-TGR)") (class "Default")
      (node (ref "U2") (pin "4") (pinfunction "TGR_4") (pintype "passive"))
      (node (ref "U3") (pin "18") (pinfunction "SH1_18") (pintype "passive"))
    )
    (net (code "92") (name "Net-(U3-AVDD)") (class "Default")
      (node (ref "C5") (pin "2") (pinfunction "2_2") (pintype "passive"))
      (node (ref "U3") (pin "12") (pinfunction "IDRIVE_12") (pintype "passive"))
      (node (ref "U3") (pin "7") (pinfunction "AVDD_7") (pintype "passive"))
    )
    (net (code "93") (name "Net-(U3-CPH)") (class "Default")
      (node (ref "C4") (pin "2") (pinfunction "2_2") (pintype "passive"))
      (node (ref "U3") (pin "3") (pinfunction "CPH_3") (pintype "passive"))
    )
    (net (code "94") (name "Net-(U3-CPL)") (class "Default")
      (node (ref "C4") (pin "1") (pinfunction "1_1") (pintype "passive"))
      (node (ref "U3") (pin "4") (pinfunction "CPL_4") (pintype "passive"))
    )
    (net (code "95") (name "Net-(U3-DVDD)") (class "Default")
      (node (ref "C6") (pin "2") (pinfunction "2_2") (pintype "passive"))
      (node (ref "R8") (pin "2") (pinfunction "2_2") (pintype "passive"))
      (node (ref "R9") (pin "2") (pinfunction "2_2") (pintype "passive"))
      (node (ref "U3") (pin "6") (pinfunction "VREF_6") (pintype "passive"))
      (node (ref "U3") (pin "8") (pinfunction "DVDD_8") (pintype "passive"))
    )
    (net (code "96") (name "Net-(U3-VCP)") (class "Default")
      (node (ref "C3") (pin "2") (pinfunction "2_2") (pintype "passive"))
      (node (ref "U3") (pin "2") (pinfunction "VCP_2") (pintype "passive"))
    )
    (net (code "97") (name "Net-(U4-BG)") (class "Default")
      (node (ref "U4") (pin "5") (pinfunction "BG_5") (pintype "passive"))
      (node (ref "U6") (pin "22") (pinfunction "GL2_22") (pintype "passive"))
    )
    (net (code "98") (name "Net-(U4-TG)") (class "Default")
      (node (ref "U4") (pin "3") (pinfunction "TG_3") (pintype "passive"))
      (node (ref "U6") (pin "24") (pinfunction "GH2_24") (pintype "passive"))
    )
    (net (code "99") (name "Net-(U4-TGR)") (class "Default")
      (node (ref "U4") (pin "4") (pinfunction "TGR_4") (pintype "passive"))
      (node (ref "U6") (pin "23") (pinfunction "SH2_23") (pintype "passive"))
    )
    (net (code "100") (name "Net-(U5-BG)") (class "Default")
      (node (ref "U5") (pin "5") (pinfunction "BG_5") (pintype "passive"))
      (node (ref "U6") (pin "19") (pinfunction "GL1_19") (pintype "passive"))
    )
    (net (code "101") (name "Net-(U5-TG)") (class "Default")
      (node (ref "U5") (pin "3") (pinfunction "TG_3") (pintype "passive"))
      (node (ref "U6") (pin "17") (pinfunction "GH1_17") (pintype "passive"))
    )
    (net (code "102") (name "Net-(U5-TGR)") (class "Default")
      (node (ref "U5") (pin "4") (pinfunction "TGR_4") (pintype "passive"))
      (node (ref "U6") (pin "18") (pinfunction "SH1_18") (pintype "passive"))
    )
    (net (code "103") (name "Net-(U6-AVDD)") (class "Default")
      (node (ref "C11") (pin "2") (pinfunction "2_2") (pintype "passive"))
      (node (ref "U6") (pin "12") (pinfunction "IDRIVE_12") (pintype "passive"))
      (node (ref "U6") (pin "7") (pinfunction "AVDD_7") (pintype "passive"))
    )
    (net (code "104") (name "Net-(U6-CPH)") (class "Default")
      (node (ref "C10") (pin "2") (pinfunction "2_2") (pintype "passive"))
      (node (ref "U6") (pin "3") (pinfunction "CPH_3") (pintype "passive"))
    )
    (net (code "105") (name "Net-(U6-CPL)") (class "Default")
      (node (ref "C10") (pin "1") (pinfunction "1_1") (pintype "passive"))
      (node (ref "U6") (pin "4") (pinfunction "CPL_4") (pintype "passive"))
    )
    (net (code "106") (name "Net-(U6-DVDD)") (class "Default")
      (node (ref "C12") (pin "2") (pinfunction "2_2") (pintype "passive"))
      (node (ref "R10") (pin "2") (pinfunction "2_2") (pintype "passive"))
      (node (ref "R11") (pin "2") (pinfunction "2_2") (pintype "passive"))
      (node (ref "R7") (pin "2") (pinfunction "2_2") (pintype "passive"))
      (node (ref "U6") (pin "6") (pinfunction "VREF_6") (pintype "passive"))
      (node (ref "U6") (pin "8") (pinfunction "DVDD_8") (pintype "passive"))
    )
    (net (code "107") (name "Net-(U6-VCP)") (class "Default")
      (node (ref "C9") (pin "2") (pinfunction "2_2") (pintype "passive"))
      (node (ref "U6") (pin "2") (pinfunction "VCP_2") (pintype "passive"))
    )
    (net (code "108") (name "Net-(U8-EN#)") (class "Default")
      (node (ref "SW2") (pin "2") (pinfunction "2_2") (pintype "passive"))
      (node (ref "U8") (pin "2") (pinfunction "EN#_2") (pintype "passive"))
    )
    (net (code "109") (name "Net-(U9-CPOUT)") (class "Default")
      (node (ref "C41") (pin "1") (pinfunction "1_1") (pintype "passive"))
      (node (ref "U9") (pin "20") (pinfunction "CPOUT_20") (pintype "passive"))
    )
    (net (code "110") (name "Net-(U9-REGOUT)") (class "Default")
      (node (ref "C43") (pin "1") (pinfunction "1_1") (pintype "passive"))
      (node (ref "U9") (pin "10") (pinfunction "REGOUT_10") (pintype "passive"))
    )
    (net (code "111") (name "VCC") (class "Default")
      (node (ref "C13") (pin "1") (pinfunction "1_1") (pintype "passive"))
      (node (ref "C14") (pin "2") (pinfunction "2_2") (pintype "passive"))
      (node (ref "C15") (pin "2") (pinfunction "2_2") (pintype "passive"))
      (node (ref "C16") (pin "1") (pinfunction "1_1") (pintype "passive"))
      (node (ref "C17") (pin "2") (pinfunction "2_2") (pintype "passive"))
      (node (ref "C18") (pin "2") (pinfunction "2_2") (pintype "passive"))
      (node (ref "C19") (pin "1") (pinfunction "1_1") (pintype "passive"))
      (node (ref "C20") (pin "1") (pinfunction "1_1") (pintype "passive"))
      (node (ref "C22") (pin "1") (pinfunction "1_1") (pintype "passive"))
      (node (ref "C23") (pin "2") (pinfunction "2_2") (pintype "passive"))
      (node (ref "C24") (pin "2") (pinfunction "2_2") (pintype "passive"))
      (node (ref "C25") (pin "1") (pinfunction "1_1") (pintype "passive"))
      (node (ref "C26") (pin "1") (pinfunction "1_1") (pintype "passive"))
      (node (ref "C29") (pin "1") (pinfunction "1_1") (pintype "passive"))
      (node (ref "C30") (pin "2") (pinfunction "2_2") (pintype "passive"))
      (node (ref "C32") (pin "1") (pinfunction "1_1") (pintype "passive"))
      (node (ref "C36") (pin "2") (pinfunction "2_2") (pintype "passive"))
      (node (ref "C42") (pin "2") (pinfunction "2_2") (pintype "passive"))
      (node (ref "C44") (pin "1") (pinfunction "1_1") (pintype "passive"))
      (node (ref "J1") (pin "2") (pinfunction "2_2") (pintype "passive"))
      (node (ref "J1") (pin "26") (pinfunction "26_26") (pintype "passive"))
      (node (ref "J1") (pin "4") (pinfunction "4_4") (pintype "passive"))
      (node (ref "J1") (pin "48") (pinfunction "48_48") (pintype "passive"))
      (node (ref "J1") (pin "6") (pinfunction "6_6") (pintype "passive"))
      (node (ref "J3") (pin "15") (pinfunction "15_15") (pintype "passive"))
      (node (ref "J3") (pin "17") (pinfunction "17_17") (pintype "passive"))
      (node (ref "J3") (pin "32") (pinfunction "32_32") (pintype "passive"))
      (node (ref "J3") (pin "33") (pinfunction "33_33") (pintype "passive"))
      (node (ref "J3") (pin "45") (pinfunction "45_45") (pintype "passive"))
      (node (ref "R12") (pin "1") (pinfunction "1_1") (pintype "passive"))
      (node (ref "R13") (pin "1") (pinfunction "1_1") (pintype "passive"))
      (node (ref "R2") (pin "1") (pinfunction "1_1") (pintype "passive"))
      (node (ref "R5") (pin "1") (pinfunction "1_1") (pintype "passive"))
      (node (ref "SW1") (pin "1") (pinfunction "1_1") (pintype "passive"))
      (node (ref "U7") (pin "1") (pinfunction "VDD_1") (pintype "passive"))
      (node (ref "U7") (pin "10") (pinfunction "USB1_AVDDC3V3_10") (pintype "passive"))
      (node (ref "U7") (pin "11") (pinfunction "USB1_AVDDTX3V3_11") (pintype "passive"))
      (node (ref "U7") (pin "21") (pinfunction "VDD_21") (pintype "passive"))
      (node (ref "U7") (pin "33") (pinfunction "VDD_33") (pintype "passive"))
      (node (ref "U7") (pin "45") (pinfunction "VBAT_45") (pintype "passive"))
      (node (ref "U7") (pin "50") (pinfunction "VDD_50") (pintype "passive"))
      (node (ref "U7") (pin "54") (pinfunction "VDD_54") (pintype "passive"))
      (node (ref "U7") (pin "75") (pinfunction "VDD_75") (pintype "passive"))
      (node (ref "U7") (pin "76") (pinfunction "VDD_76") (pintype "passive"))
      (node (ref "U7") (pin "9") (pinfunction "USB1_VBUS_9") (pintype "passive"))
      (node (ref "U7") (pin "99") (pinfunction "VDD_99") (pintype "passive"))
      (node (ref "U8") (pin "5") (pinfunction "OUT_5") (pintype "passive"))
      (node (ref "U8") (pin "6") (pinfunction "OUT_6") (pintype "passive"))
      (node (ref "U9") (pin "13") (pinfunction "VDD_13") (pintype "passive"))
      (node (ref "U9") (pin "8") (pinfunction "VLOGIC_8") (pintype "passive"))
    )
    (net (code "112") (name "unconnected-(U3-SNSOUT-Pad10)") (class "Default")
      (node (ref "U3") (pin "10") (pinfunction "SNSOUT_10") (pintype "passive"))
    )
    (net (code "113") (name "unconnected-(U3-SO-Pad11)") (class "Default")
      (node (ref "U3") (pin "11") (pinfunction "SO_11") (pintype "passive"))
    )
    (net (code "114") (name "unconnected-(U6-SNSOUT-Pad10)") (class "Default")
      (node (ref "U6") (pin "10") (pinfunction "SNSOUT_10") (pintype "passive"))
    )
    (net (code "115") (name "unconnected-(U6-SO-Pad11)") (class "Default")
      (node (ref "U6") (pin "11") (pinfunction "SO_11") (pintype "passive"))
    )
    (net (code "116") (name "unconnected-(U7-USB0_DM-Pad98)") (class "Default")
      (node (ref "U7") (pin "98") (pinfunction "USB0_DM_98") (pintype "passive"))
    )
    (net (code "117") (name "unconnected-(U7-USB0_DP-Pad97)") (class "Default")
      (node (ref "U7") (pin "97") (pinfunction "USB0_DP_97") (pintype "passive"))
    )
    (net (code "118") (name "unconnected-(U7-USB1_DM-Pad12)") (class "Default")
      (node (ref "U7") (pin "12") (pinfunction "USB1_DM_12") (pintype "passive"))
    )
    (net (code "119") (name "unconnected-(U7-USB1_DP-Pad13)") (class "Default")
      (node (ref "U7") (pin "13") (pinfunction "USB1_DP_13") (pintype "passive"))
    )
    (net (code "120") (name "unconnected-(U7-USB1_ID-Pad8)") (class "Default")
      (node (ref "U7") (pin "8") (pinfunction "USB1_ID_8") (pintype "passive"))
    )
    (net (code "121") (name "unconnected-(U7-USB1_RETX-Pad7)") (class "Default")
      (node (ref "U7") (pin "7") (pinfunction "USB1_RETX_7") (pintype "passive"))
    )
    (net (code "122") (name "unconnected-(U8-FB{slash}NC-Pad7)") (class "Default")
      (node (ref "U8") (pin "7") (pinfunction "FB/NC_7") (pintype "passive"))
    )
    (net (code "123") (name "unconnected-(U9-A-CL-Pad7)") (class "Default")
      (node (ref "U9") (pin "7") (pinfunction "A-CL_7") (pintype "passive"))
    )
    (net (code "124") (name "unconnected-(U9-A_DA-Pad6)") (class "Default")
      (node (ref "U9") (pin "6") (pinfunction "A_DA_6") (pintype "passive"))
    )
    (net (code "125") (name "unconnected-(U9-CLKOUT-Pad22)") (class "Default")
      (node (ref "U9") (pin "22") (pinfunction "CLKOUT_22") (pintype "passive"))
    )
    (net (code "126") (name "unconnected-(U9-NC-Pad2)") (class "Default")
      (node (ref "U9") (pin "2") (pinfunction "NC_2") (pintype "passive"))
    )
    (net (code "127") (name "unconnected-(U9-NC-Pad3)") (class "Default")
      (node (ref "U9") (pin "3") (pinfunction "NC_3") (pintype "passive"))
    )
    (net (code "128") (name "unconnected-(U9-NC-Pad4)") (class "Default")
      (node (ref "U9") (pin "4") (pinfunction "NC_4") (pintype "passive"))
    )
    (net (code "129") (name "unconnected-(U9-NC-Pad5)") (class "Default")
      (node (ref "U9") (pin "5") (pinfunction "NC_5") (pintype "passive"))
    )
    (net (code "130") (name "unconnected-(U9-NC-Pad14)") (class "Default")
      (node (ref "U9") (pin "14") (pinfunction "NC_14") (pintype "passive"))
    )
    (net (code "131") (name "unconnected-(U9-NC-Pad15)") (class "Default")
      (node (ref "U9") (pin "15") (pinfunction "NC_15") (pintype "passive"))
    )
    (net (code "132") (name "unconnected-(U9-NC-Pad16)") (class "Default")
      (node (ref "U9") (pin "16") (pinfunction "NC_16") (pintype "passive"))
    )
    (net (code "133") (name "unconnected-(U9-NC-Pad17)") (class "Default")
      (node (ref "U9") (pin "17") (pinfunction "NC_17") (pintype "passive"))
    )
    (net (code "134") (name "unconnected-(U9-RESV-Pad19)") (class "Default")
      (node (ref "U9") (pin "19") (pinfunction "RESV_19") (pintype "passive"))
    )
    (net (code "135") (name "unconnected-(U9-RESV-Pad21)") (class "Default")
      (node (ref "U9") (pin "21") (pinfunction "RESV_21") (pintype "passive"))
    )
  )
)
